# TempSensor.net
KiCad netlist of a schematic drawn in Altium Designer
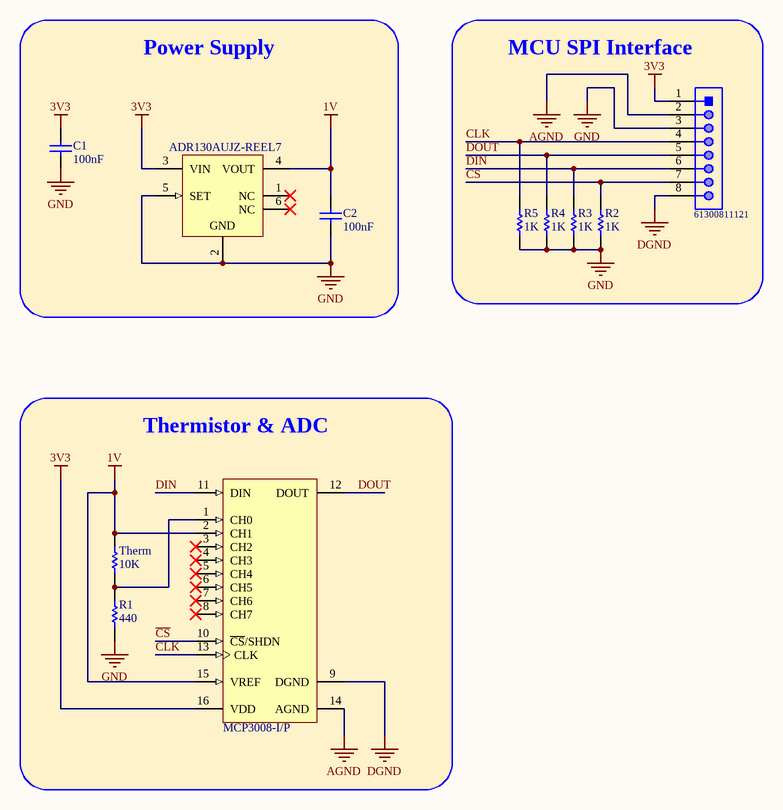
[diagram p0: TempSensor.SchDoc]

(export (version "E")
  (design (tool "Eeschema 10.0.6"))
  (components
    (comp (ref "ADC")
      (value "MCP3008-I/P")
      (footprint "PDIP300-P16")
      (libsource (lib "Altium Content Vault") (part "CON-ADC-MCP3008-16"))
    )
    (comp (ref "C1")
      (value "100nF")
      (footprint "RAD-0.3")
      (description "Capacitor")
      (fields (field (name "Comment") "Cap") (field (name "PUBLISHER") "Altium Limited"))
      (libsource (lib "Miscellaneous Devices") (part "Cap"))
    )
    (comp (ref "C2")
      (value "100nF")
      (footprint "RAD-0.3")
      (description "Capacitor")
      (fields (field (name "Comment") "Cap") (field (name "PUBLISHER") "Altium Limited"))
      (libsource (lib "Miscellaneous Devices") (part "Cap"))
    )
    (comp (ref "Pins")
      (value "61300811121")
      (footprint "61300811121")
      (description "THT Vertical Pin Header WR-PHD, Pitch 2.54 mm, Single Row, 8 pins")
      (fields (field (name "MANUFACTURER") "Wurth Elektronik") (field (name "PUBLISHER") "WurthElektronik"))
      (libsource (lib "Altium Content Vault") (part "WE-CN-1P-M-R8"))
    )
    (comp (ref "R1")
      (value "440")
      (footprint "AXIAL-0.3")
      (description "Resistor")
      (fields (field (name "Comment") "Res1") (field (name "PUBLISHER") "Altium Limited"))
      (libsource (lib "Miscellaneous Devices") (part "Res1"))
    )
    (comp (ref "R2")
      (value "1K")
      (footprint "AXIAL-0.3")
      (description "Resistor")
      (fields (field (name "Comment") "Res1") (field (name "PUBLISHER") "Altium Limited"))
      (libsource (lib "Miscellaneous Devices") (part "Res1"))
    )
    (comp (ref "R3")
      (value "1K")
      (footprint "AXIAL-0.3")
      (description "Resistor")
      (fields (field (name "Comment") "Res1") (field (name "PUBLISHER") "Altium Limited"))
      (libsource (lib "Miscellaneous Devices") (part "Res1"))
    )
    (comp (ref "R4")
      (value "1K")
      (footprint "AXIAL-0.3")
      (description "Resistor")
      (fields (field (name "Comment") "Res1") (field (name "PUBLISHER") "Altium Limited"))
      (libsource (lib "Miscellaneous Devices") (part "Res1"))
    )
    (comp (ref "R5")
      (value "1K")
      (footprint "AXIAL-0.3")
      (description "Resistor")
      (fields (field (name "Comment") "Res1") (field (name "PUBLISHER") "Altium Limited"))
      (libsource (lib "Miscellaneous Devices") (part "Res1"))
    )
    (comp (ref "Therm")
      (value "10K")
      (footprint "AXIAL-0.3")
      (description "Thermistor")
      (fields (field (name "PUBLISHER") "Altium Limited"))
      (libsource (lib "Miscellaneous Devices") (part "Res1"))
    )
    (comp (ref "Vref")
      (value "ADR130AUJZ-REEL7")
      (footprint "ADI-UJ-6_M")
      (fields (field (name "MANUFACTURER") "Analog Devices"))
      (libsource (lib "Altium Content Vault") (part "ADI-ADR130-UJ-6"))
    )
  )
  (nets
    (net (code "1") (name "/CLK") (class "Default")
      (node (ref "ADC") (pin "13") (pinfunction "CLK_13") (pintype "input"))
      (node (ref "Pins") (pin "4") (pinfunction "4_4") (pintype "passive"))
      (node (ref "R5") (pin "2") (pinfunction "2_2") (pintype "passive"))
    )
    (net (code "2") (name "/CS") (class "Default")
      (node (ref "ADC") (pin "10") (pinfunction "~{CS}/SHDN_10") (pintype "input"))
      (node (ref "Pins") (pin "7") (pinfunction "7_7") (pintype "passive"))
      (node (ref "R2") (pin "2") (pinfunction "2_2") (pintype "passive"))
    )
    (net (code "3") (name "/DIN") (class "Default")
      (node (ref "ADC") (pin "11") (pinfunction "DIN_11") (pintype "input"))
      (node (ref "Pins") (pin "6") (pinfunction "6_6") (pintype "passive"))
      (node (ref "R3") (pin "2") (pinfunction "2_2") (pintype "passive"))
    )
    (net (code "4") (name "/DOUT") (class "Default")
      (node (ref "ADC") (pin "12") (pinfunction "DOUT_12") (pintype "tri_state"))
      (node (ref "Pins") (pin "5") (pinfunction "5_5") (pintype "passive"))
      (node (ref "R4") (pin "2") (pinfunction "2_2") (pintype "passive"))
    )
    (net (code "5") (name "1V") (class "Default")
      (node (ref "ADC") (pin "15") (pinfunction "VREF_15") (pintype "input"))
      (node (ref "ADC") (pin "2") (pinfunction "CH1_2") (pintype "input"))
      (node (ref "C2") (pin "2") (pinfunction "2_2") (pintype "passive"))
      (node (ref "Therm") (pin "2") (pinfunction "2_2") (pintype "passive"))
      (node (ref "Vref") (pin "4") (pinfunction "VOUT_4") (pintype "power_in"))
    )
    (net (code "6") (name "3V3") (class "Default")
      (node (ref "ADC") (pin "16") (pinfunction "VDD_16") (pintype "power_in"))
      (node (ref "C1") (pin "2") (pinfunction "2_2") (pintype "passive"))
      (node (ref "Pins") (pin "1") (pinfunction "1_1") (pintype "passive"))
      (node (ref "Vref") (pin "3") (pinfunction "VIN_3") (pintype "power_in"))
    )
    (net (code "7") (name "AGND") (class "Default")
      (node (ref "ADC") (pin "14") (pinfunction "AGND_14") (pintype "power_in"))
      (node (ref "Pins") (pin "2") (pinfunction "2_2") (pintype "passive"))
    )
    (net (code "8") (name "DGND") (class "Default")
      (node (ref "ADC") (pin "9") (pinfunction "DGND_9") (pintype "power_in"))
      (node (ref "Pins") (pin "8") (pinfunction "8_8") (pintype "passive"))
    )
    (net (code "9") (name "GND") (class "Default")
      (node (ref "C1") (pin "1") (pinfunction "1_1") (pintype "passive"))
      (node (ref "C2") (pin "1") (pinfunction "1_1") (pintype "passive"))
      (node (ref "Pins") (pin "3") (pinfunction "3_3") (pintype "passive"))
      (node (ref "R1") (pin "1") (pinfunction "1_1") (pintype "passive"))
      (node (ref "R2") (pin "1") (pinfunction "1_1") (pintype "passive"))
      (node (ref "R3") (pin "1") (pinfunction "1_1") (pintype "passive"))
      (node (ref "R4") (pin "1") (pinfunction "1_1") (pintype "passive"))
      (node (ref "R5") (pin "1") (pinfunction "1_1") (pintype "passive"))
      (node (ref "Vref") (pin "2") (pinfunction "GND_2") (pintype "power_in"))
      (node (ref "Vref") (pin "5") (pinfunction "SET_5") (pintype "input"))
    )
    (net (code "10") (name "Net-(ADC-CH0)") (class "Default")
      (node (ref "ADC") (pin "1") (pinfunction "CH0_1") (pintype "input"))
      (node (ref "R1") (pin "2") (pinfunction "2_2") (pintype "passive"))
      (node (ref "Therm") (pin "1") (pinfunction "1_1") (pintype "passive"))
    )
    (net (code "11") (name "unconnected-(ADC-CH2-Pad3)") (class "Default")
      (node (ref "ADC") (pin "3") (pinfunction "CH2_3") (pintype "input+no_connect"))
    )
    (net (code "12") (name "unconnected-(ADC-CH3-Pad4)") (class "Default")
      (node (ref "ADC") (pin "4") (pinfunction "CH3_4") (pintype "input+no_connect"))
    )
    (net (code "13") (name "unconnected-(ADC-CH4-Pad5)") (class "Default")
      (node (ref "ADC") (pin "5") (pinfunction "CH4_5") (pintype "input+no_connect"))
    )
    (net (code "14") (name "unconnected-(ADC-CH5-Pad6)") (class "Default")
      (node (ref "ADC") (pin "6") (pinfunction "CH5_6") (pintype "input+no_connect"))
    )
    (net (code "15") (name "unconnected-(ADC-CH6-Pad7)") (class "Default")
      (node (ref "ADC") (pin "7") (pinfunction "CH6_7") (pintype "input+no_connect"))
    )
    (net (code "16") (name "unconnected-(ADC-CH7-Pad8)") (class "Default")
      (node (ref "ADC") (pin "8") (pinfunction "CH7_8") (pintype "input+no_connect"))
    )
    (net (code "17") (name "unconnected-(Vref-NC-Pad1)") (class "Default")
      (node (ref "Vref") (pin "1") (pinfunction "NC_1") (pintype "passive+no_connect"))
    )
    (net (code "18") (name "unconnected-(Vref-NC-Pad6)") (class "Default")
      (node (ref "Vref") (pin "6") (pinfunction "NC_6") (pintype "passive+no_connect"))
    )
  )
)
